# 401_GridPos4.net
KiCad netlist of a schematic drawn in Altium Designer
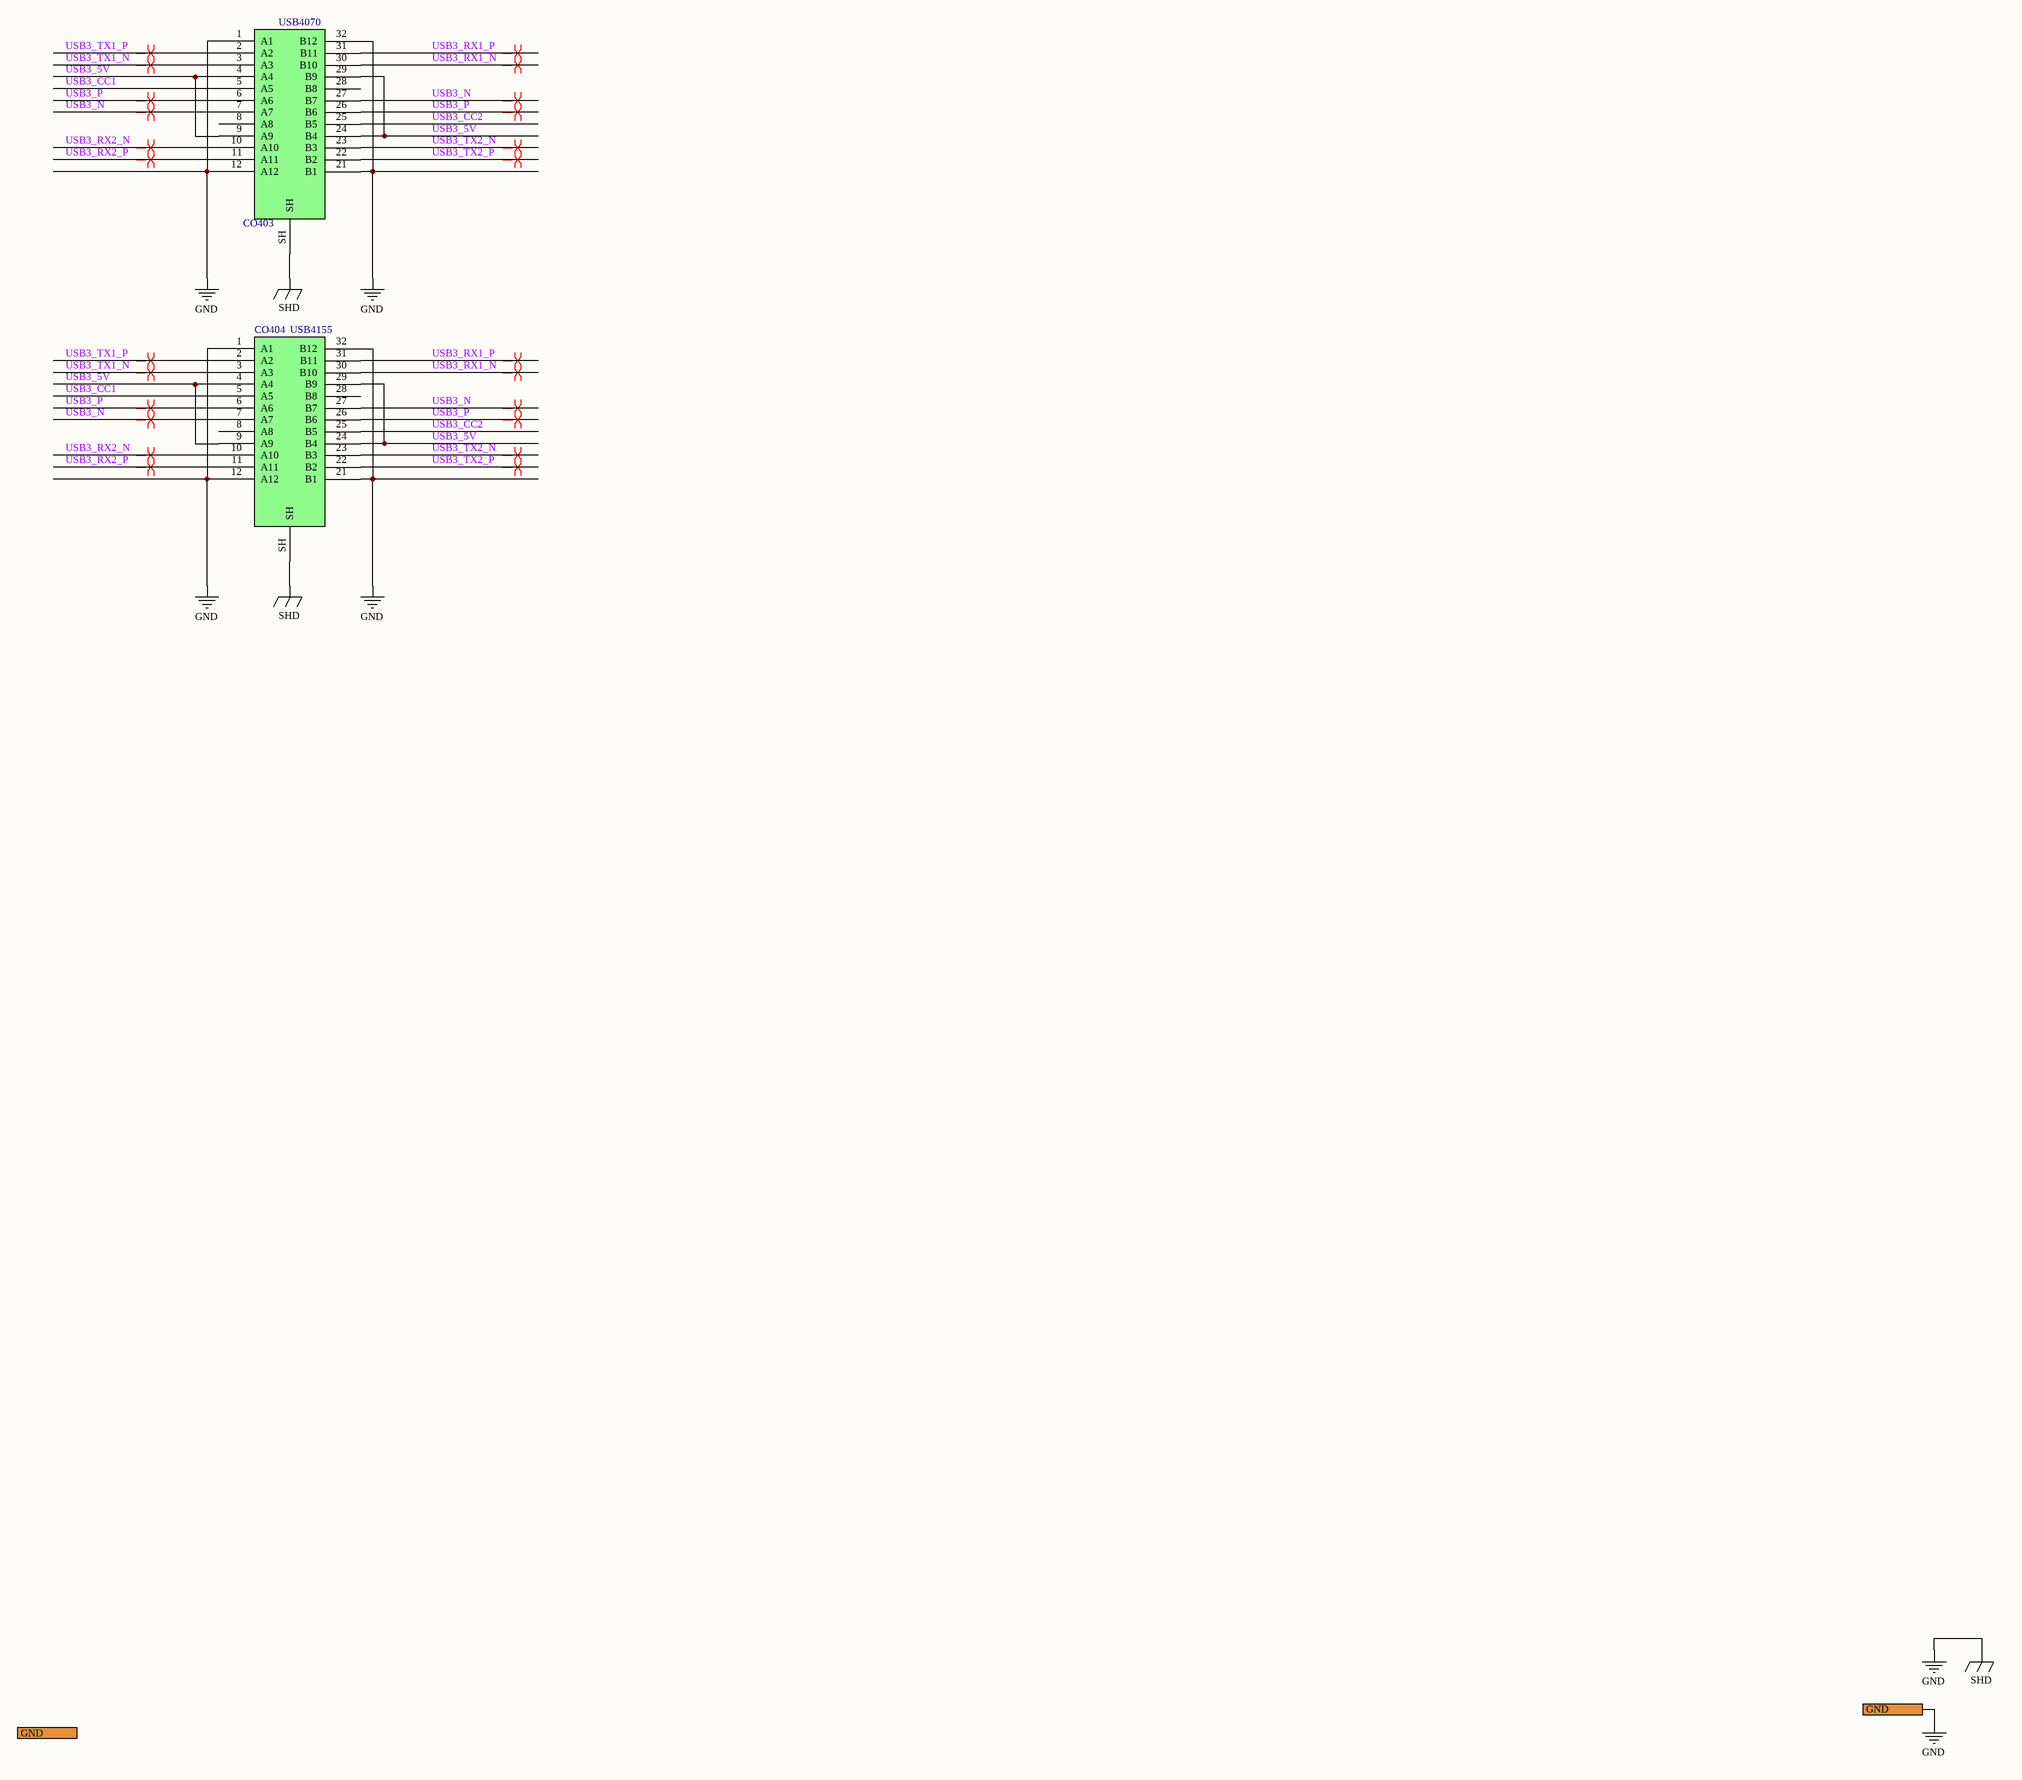
[diagram p0: 401_GridPos4.SchDoc]

(export (version "E")
  (design (tool "Eeschema 10.0.6"))
  (components
    (comp (ref "CO403")
      (value "USB4070")
      (footprint "USB4070-30-C")
      (description "USB C connector Receptacle Vertical")
      (fields
        (field (name "REFVAL") "USB4070")
        (field (name "PART NUMBER") "CO0021")
        (field (name "MANFACTPART") "USB4070-30-C")
      )
      (libsource (lib "GTS_Database") (part "USB-CC"))
    )
    (comp (ref "CO404")
      (value "USB4155")
      (footprint "USB4155-03-C")
      (description "USB C connector Plug Horizontal")
      (fields
        (field (name "REFVAL") "USB4155")
        (field (name "PART NUMBER") "CO0031")
        (field (name "MANFACTPART") "USB4155-03-C")
      )
      (libsource (lib "GTS_Database") (part "USB-CC"))
    )
  )
  (nets
    (net (code "1") (name "/USB3_5V") (class "Default")
      (node (ref "CO403") (pin "24") (pinfunction "B4_24") (pintype "passive"))
      (node (ref "CO403") (pin "29") (pinfunction "B9_29") (pintype "passive"))
      (node (ref "CO403") (pin "4") (pinfunction "A4_4") (pintype "passive"))
      (node (ref "CO403") (pin "9") (pinfunction "A9_9") (pintype "passive"))
      (node (ref "CO404") (pin "24") (pinfunction "B4_24") (pintype "passive"))
      (node (ref "CO404") (pin "29") (pinfunction "B9_29") (pintype "passive"))
      (node (ref "CO404") (pin "4") (pinfunction "A4_4") (pintype "passive"))
      (node (ref "CO404") (pin "9") (pinfunction "A9_9") (pintype "passive"))
    )
    (net (code "2") (name "/USB3_CC1") (class "Default")
      (node (ref "CO403") (pin "5") (pinfunction "A5_5") (pintype "passive"))
      (node (ref "CO404") (pin "5") (pinfunction "A5_5") (pintype "passive"))
    )
    (net (code "3") (name "/USB3_CC2") (class "Default")
      (node (ref "CO403") (pin "25") (pinfunction "B5_25") (pintype "passive"))
      (node (ref "CO404") (pin "25") (pinfunction "B5_25") (pintype "passive"))
    )
    (net (code "4") (name "/USB3_N") (class "Default")
      (node (ref "CO403") (pin "27") (pinfunction "B7_27") (pintype "passive"))
      (node (ref "CO403") (pin "7") (pinfunction "A7_7") (pintype "passive"))
      (node (ref "CO404") (pin "27") (pinfunction "B7_27") (pintype "passive"))
      (node (ref "CO404") (pin "7") (pinfunction "A7_7") (pintype "passive"))
    )
    (net (code "5") (name "/USB3_P") (class "Default")
      (node (ref "CO403") (pin "26") (pinfunction "B6_26") (pintype "passive"))
      (node (ref "CO403") (pin "6") (pinfunction "A6_6") (pintype "passive"))
      (node (ref "CO404") (pin "26") (pinfunction "B6_26") (pintype "passive"))
      (node (ref "CO404") (pin "6") (pinfunction "A6_6") (pintype "passive"))
    )
    (net (code "6") (name "/USB3_RX1_N") (class "Default")
      (node (ref "CO403") (pin "30") (pinfunction "B10_30") (pintype "passive"))
      (node (ref "CO404") (pin "30") (pinfunction "B10_30") (pintype "passive"))
    )
    (net (code "7") (name "/USB3_RX1_P") (class "Default")
      (node (ref "CO403") (pin "31") (pinfunction "B11_31") (pintype "passive"))
      (node (ref "CO404") (pin "31") (pinfunction "B11_31") (pintype "passive"))
    )
    (net (code "8") (name "/USB3_RX2_N") (class "Default")
      (node (ref "CO403") (pin "10") (pinfunction "A10_10") (pintype "passive"))
      (node (ref "CO404") (pin "10") (pinfunction "A10_10") (pintype "passive"))
    )
    (net (code "9") (name "/USB3_RX2_P") (class "Default")
      (node (ref "CO403") (pin "11") (pinfunction "A11_11") (pintype "passive"))
      (node (ref "CO404") (pin "11") (pinfunction "A11_11") (pintype "passive"))
    )
    (net (code "10") (name "/USB3_TX1_N") (class "Default")
      (node (ref "CO403") (pin "3") (pinfunction "A3_3") (pintype "passive"))
      (node (ref "CO404") (pin "3") (pinfunction "A3_3") (pintype "passive"))
    )
    (net (code "11") (name "/USB3_TX1_P") (class "Default")
      (node (ref "CO403") (pin "2") (pinfunction "A2_2") (pintype "passive"))
      (node (ref "CO404") (pin "2") (pinfunction "A2_2") (pintype "passive"))
    )
    (net (code "12") (name "/USB3_TX2_N") (class "Default")
      (node (ref "CO403") (pin "23") (pinfunction "B3_23") (pintype "passive"))
      (node (ref "CO404") (pin "23") (pinfunction "B3_23") (pintype "passive"))
    )
    (net (code "13") (name "/USB3_TX2_P") (class "Default")
      (node (ref "CO403") (pin "22") (pinfunction "B2_22") (pintype "passive"))
      (node (ref "CO404") (pin "22") (pinfunction "B2_22") (pintype "passive"))
    )
    (net (code "14") (name "GND") (class "Default")
      (node (ref "CO403") (pin "1") (pinfunction "A1_1") (pintype "passive"))
      (node (ref "CO403") (pin "12") (pinfunction "A12_12") (pintype "passive"))
      (node (ref "CO403") (pin "21") (pinfunction "B1_21") (pintype "passive"))
      (node (ref "CO403") (pin "32") (pinfunction "B12_32") (pintype "passive"))
      (node (ref "CO403") (pin "SH") (pinfunction "SH_SH") (pintype "power_in"))
      (node (ref "CO404") (pin "1") (pinfunction "A1_1") (pintype "passive"))
      (node (ref "CO404") (pin "12") (pinfunction "A12_12") (pintype "passive"))
      (node (ref "CO404") (pin "21") (pinfunction "B1_21") (pintype "passive"))
      (node (ref "CO404") (pin "32") (pinfunction "B12_32") (pintype "passive"))
      (node (ref "CO404") (pin "SH") (pinfunction "SH_SH") (pintype "power_in"))
    )
    (net (code "15") (name "unconnected-(CO403-A8-Pad8)") (class "Default")
      (node (ref "CO403") (pin "8") (pinfunction "A8_8") (pintype "passive"))
    )
    (net (code "16") (name "unconnected-(CO403-B8-Pad28)") (class "Default")
      (node (ref "CO403") (pin "28") (pinfunction "B8_28") (pintype "passive"))
    )
    (net (code "17") (name "unconnected-(CO404-A8-Pad8)") (class "Default")
      (node (ref "CO404") (pin "8") (pinfunction "A8_8") (pintype "passive"))
    )
    (net (code "18") (name "unconnected-(CO404-B8-Pad28)") (class "Default")
      (node (ref "CO404") (pin "28") (pinfunction "B8_28") (pintype "passive"))
    )
  )
)
